# 26P2.net
KiCad netlist of a schematic drawn in Altium Designer
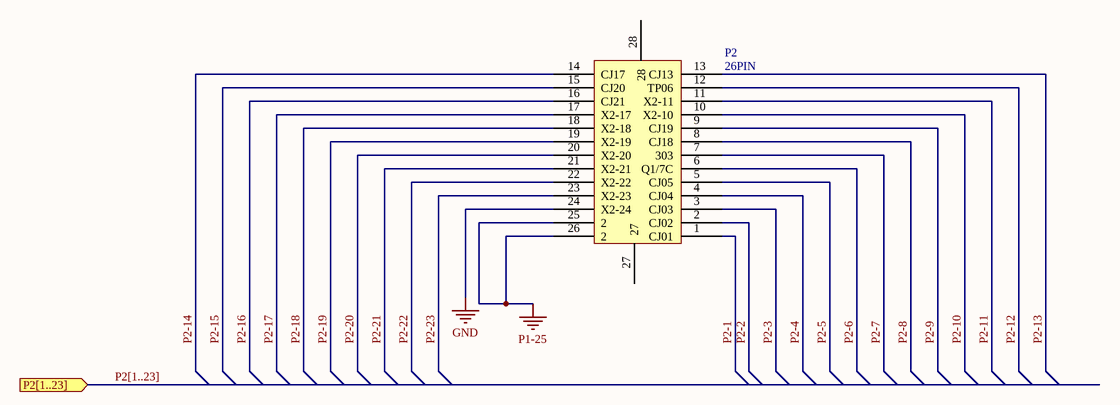
[diagram p0: 26P2.SchDoc]

(export (version "E")
  (design (tool "Eeschema 10.0.6"))
  (components
    (comp (ref "P2")
      (value "26PIN")
      (footprint "采集板3.0增加1路模拟量2:2*13")
      (libsource (lib "26PIN") (part "Component_1"))
    )
  )
  (nets
    (net (code "24") (name "/P2-1") (class "Default")
      (node (ref "P2") (pin "1") (pinfunction "CJ01_1") (pintype "passive"))
    )
    (net (code "25") (name "/P2-2") (class "Default")
      (node (ref "P2") (pin "2") (pinfunction "CJ02_2") (pintype "passive"))
    )
    (net (code "26") (name "/P2-3") (class "Default")
      (node (ref "P2") (pin "3") (pinfunction "CJ03_3") (pintype "passive"))
    )
    (net (code "27") (name "/P2-4") (class "Default")
      (node (ref "P2") (pin "4") (pinfunction "CJ04_4") (pintype "passive"))
    )
    (net (code "28") (name "/P2-5") (class "Default")
      (node (ref "P2") (pin "5") (pinfunction "CJ05_5") (pintype "passive"))
    )
    (net (code "29") (name "/P2-6") (class "Default")
      (node (ref "P2") (pin "6") (pinfunction "Q1/7C_6") (pintype "passive"))
    )
    (net (code "30") (name "/P2-7") (class "Default")
      (node (ref "P2") (pin "7") (pinfunction "303_7") (pintype "passive"))
    )
    (net (code "31") (name "/P2-8") (class "Default")
      (node (ref "P2") (pin "8") (pinfunction "CJ18_8") (pintype "passive"))
    )
    (net (code "32") (name "/P2-9") (class "Default")
      (node (ref "P2") (pin "9") (pinfunction "CJ19_9") (pintype "passive"))
    )
    (net (code "33") (name "/P2-10") (class "Default")
      (node (ref "P2") (pin "10") (pinfunction "X2-10_10") (pintype "passive"))
    )
    (net (code "34") (name "/P2-11") (class "Default")
      (node (ref "P2") (pin "11") (pinfunction "X2-11_11") (pintype "passive"))
    )
    (net (code "35") (name "/P2-12") (class "Default")
      (node (ref "P2") (pin "12") (pinfunction "TP06_12") (pintype "passive"))
    )
    (net (code "36") (name "/P2-13") (class "Default")
      (node (ref "P2") (pin "13") (pinfunction "CJ13_13") (pintype "passive"))
    )
    (net (code "37") (name "/P2-14") (class "Default")
      (node (ref "P2") (pin "14") (pinfunction "CJ17_14") (pintype "passive"))
    )
    (net (code "38") (name "/P2-15") (class "Default")
      (node (ref "P2") (pin "15") (pinfunction "CJ20_15") (pintype "passive"))
    )
    (net (code "39") (name "/P2-16") (class "Default")
      (node (ref "P2") (pin "16") (pinfunction "CJ21_16") (pintype "passive"))
    )
    (net (code "40") (name "/P2-17") (class "Default")
      (node (ref "P2") (pin "17") (pinfunction "X2-17_17") (pintype "passive"))
    )
    (net (code "41") (name "/P2-18") (class "Default")
      (node (ref "P2") (pin "18") (pinfunction "X2-18_18") (pintype "passive"))
    )
    (net (code "42") (name "/P2-19") (class "Default")
      (node (ref "P2") (pin "19") (pinfunction "X2-19_19") (pintype "passive"))
    )
    (net (code "43") (name "/P2-20") (class "Default")
      (node (ref "P2") (pin "20") (pinfunction "X2-20_20") (pintype "passive"))
    )
    (net (code "44") (name "/P2-21") (class "Default")
      (node (ref "P2") (pin "21") (pinfunction "X2-21_21") (pintype "passive"))
    )
    (net (code "45") (name "/P2-22") (class "Default")
      (node (ref "P2") (pin "22") (pinfunction "X2-22_22") (pintype "passive"))
    )
    (net (code "46") (name "/P2-23") (class "Default")
      (node (ref "P2") (pin "23") (pinfunction "X2-23_23") (pintype "passive"))
    )
    (net (code "48") (name "GND") (class "Default")
      (node (ref "P2") (pin "24") (pinfunction "X2-24_24") (pintype "passive"))
    )
    (net (code "49") (name "P1-25") (class "Default")
      (node (ref "P2") (pin "25") (pinfunction "2_25") (pintype "passive"))
      (node (ref "P2") (pin "26") (pinfunction "2_26") (pintype "passive"))
    )
    (net (code "50") (name "unconnected-(P2-Pad27)") (class "Default")
      (node (ref "P2") (pin "27") (pinfunction "27_27") (pintype "passive"))
    )
    (net (code "51") (name "unconnected-(P2-Pad28)") (class "Default")
      (node (ref "P2") (pin "28") (pinfunction "28_28") (pintype "passive"))
    )
  )
)
